# lcd_ch.net
KiCad netlist of a schematic drawn in Altium Designer
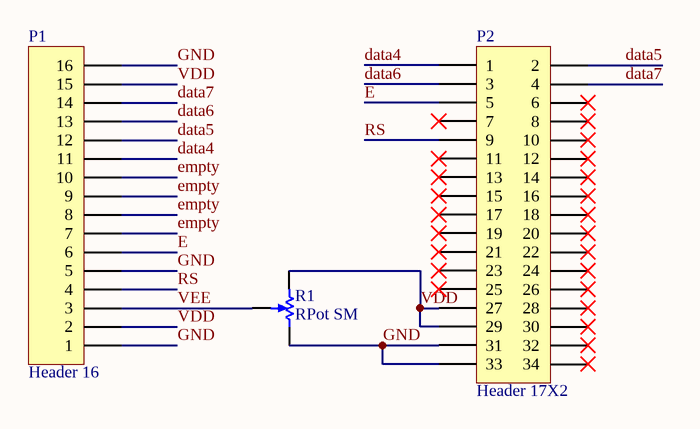
[diagram p0: lcd_ch.SchDoc]

(export (version "E")
  (design (tool "Eeschema 10.0.6"))
  (components
    (comp (ref "P1")
      (value "Header 16")
      (footprint "HDR1X16")
      (description "Header, 16-Pin")
      (fields (field (name "PUBLISHER") "Altium Limited"))
      (libsource (lib "Miscellaneous Connectors") (part "Header 16"))
    )
    (comp (ref "P2")
      (value "Header 17X2")
      (footprint "HDR2X17")
      (description "Header, 17-Pin, Dual row")
      (fields (field (name "PUBLISHER") "Altium Limited"))
      (libsource (lib "Miscellaneous Connectors") (part "Header 17X2"))
    )
    (comp (ref "R1")
      (value "RPot SM")
      (footprint "pot")
      (description "Square Trimming Potentiometer")
      (fields (field (name "PUBLISHER") "Altium Limited"))
      (libsource (lib "Miscellaneous Devices") (part "RPot SM"))
    )
  )
  (nets
    (net (code "2") (name "/E") (class "Default")
      (node (ref "P1") (pin "6") (pinfunction "6_6") (pintype "passive"))
      (node (ref "P2") (pin "5") (pinfunction "5_5") (pintype "passive"))
    )
    (net (code "3") (name "/GND") (class "Default")
      (node (ref "P1") (pin "1") (pinfunction "1_1") (pintype "passive"))
      (node (ref "P1") (pin "16") (pinfunction "16_16") (pintype "passive"))
      (node (ref "P1") (pin "5") (pinfunction "5_5") (pintype "passive"))
      (node (ref "P2") (pin "31") (pinfunction "31_31") (pintype "passive"))
      (node (ref "P2") (pin "33") (pinfunction "33_33") (pintype "passive"))
      (node (ref "R1") (pin "CW") (pinfunction "+_CW") (pintype "passive"))
    )
    (net (code "4") (name "/RS") (class "Default")
      (node (ref "P1") (pin "4") (pinfunction "4_4") (pintype "passive"))
      (node (ref "P2") (pin "9") (pinfunction "9_9") (pintype "passive"))
    )
    (net (code "5") (name "/VDD") (class "Default")
      (node (ref "P1") (pin "15") (pinfunction "15_15") (pintype "passive"))
      (node (ref "P1") (pin "2") (pinfunction "2_2") (pintype "passive"))
      (node (ref "P2") (pin "27") (pinfunction "27_27") (pintype "passive"))
      (node (ref "P2") (pin "29") (pinfunction "29_29") (pintype "passive"))
      (node (ref "R1") (pin "CCW") (pinfunction "-_CCW") (pintype "passive"))
    )
    (net (code "6") (name "/VEE") (class "Default")
      (node (ref "P1") (pin "3") (pinfunction "3_3") (pintype "passive"))
      (node (ref "R1") (pin "W") (pinfunction "W_W") (pintype "passive"))
    )
    (net (code "7") (name "/data4") (class "Default")
      (node (ref "P1") (pin "11") (pinfunction "11_11") (pintype "passive"))
      (node (ref "P2") (pin "1") (pinfunction "1_1") (pintype "passive"))
    )
    (net (code "8") (name "/data5") (class "Default")
      (node (ref "P1") (pin "12") (pinfunction "12_12") (pintype "passive"))
      (node (ref "P2") (pin "2") (pinfunction "2_2") (pintype "passive"))
    )
    (net (code "9") (name "/data6") (class "Default")
      (node (ref "P1") (pin "13") (pinfunction "13_13") (pintype "passive"))
      (node (ref "P2") (pin "3") (pinfunction "3_3") (pintype "passive"))
    )
    (net (code "10") (name "/data7") (class "Default")
      (node (ref "P1") (pin "14") (pinfunction "14_14") (pintype "passive"))
      (node (ref "P2") (pin "4") (pinfunction "4_4") (pintype "passive"))
    )
    (net (code "11") (name "/empty") (class "Default")
      (node (ref "P1") (pin "10") (pinfunction "10_10") (pintype "passive"))
      (node (ref "P1") (pin "7") (pinfunction "7_7") (pintype "passive"))
      (node (ref "P1") (pin "8") (pinfunction "8_8") (pintype "passive"))
      (node (ref "P1") (pin "9") (pinfunction "9_9") (pintype "passive"))
    )
    (net (code "12") (name "unconnected-(P2-Pad6)") (class "Default")
      (node (ref "P2") (pin "6") (pinfunction "6_6") (pintype "passive+no_connect"))
    )
    (net (code "13") (name "unconnected-(P2-Pad7)") (class "Default")
      (node (ref "P2") (pin "7") (pinfunction "7_7") (pintype "passive+no_connect"))
    )
    (net (code "14") (name "unconnected-(P2-Pad8)") (class "Default")
      (node (ref "P2") (pin "8") (pinfunction "8_8") (pintype "passive+no_connect"))
    )
    (net (code "15") (name "unconnected-(P2-Pad10)") (class "Default")
      (node (ref "P2") (pin "10") (pinfunction "10_10") (pintype "passive+no_connect"))
    )
    (net (code "16") (name "unconnected-(P2-Pad11)") (class "Default")
      (node (ref "P2") (pin "11") (pinfunction "11_11") (pintype "passive+no_connect"))
    )
    (net (code "17") (name "unconnected-(P2-Pad12)") (class "Default")
      (node (ref "P2") (pin "12") (pinfunction "12_12") (pintype "passive+no_connect"))
    )
    (net (code "18") (name "unconnected-(P2-Pad13)") (class "Default")
      (node (ref "P2") (pin "13") (pinfunction "13_13") (pintype "passive+no_connect"))
    )
    (net (code "19") (name "unconnected-(P2-Pad14)") (class "Default")
      (node (ref "P2") (pin "14") (pinfunction "14_14") (pintype "passive+no_connect"))
    )
    (net (code "20") (name "unconnected-(P2-Pad15)") (class "Default")
      (node (ref "P2") (pin "15") (pinfunction "15_15") (pintype "passive+no_connect"))
    )
    (net (code "21") (name "unconnected-(P2-Pad16)") (class "Default")
      (node (ref "P2") (pin "16") (pinfunction "16_16") (pintype "passive+no_connect"))
    )
    (net (code "22") (name "unconnected-(P2-Pad17)") (class "Default")
      (node (ref "P2") (pin "17") (pinfunction "17_17") (pintype "passive+no_connect"))
    )
    (net (code "23") (name "unconnected-(P2-Pad18)") (class "Default")
      (node (ref "P2") (pin "18") (pinfunction "18_18") (pintype "passive+no_connect"))
    )
    (net (code "24") (name "unconnected-(P2-Pad19)") (class "Default")
      (node (ref "P2") (pin "19") (pinfunction "19_19") (pintype "passive+no_connect"))
    )
    (net (code "25") (name "unconnected-(P2-Pad20)") (class "Default")
      (node (ref "P2") (pin "20") (pinfunction "20_20") (pintype "passive+no_connect"))
    )
    (net (code "26") (name "unconnected-(P2-Pad21)") (class "Default")
      (node (ref "P2") (pin "21") (pinfunction "21_21") (pintype "passive+no_connect"))
    )
    (net (code "27") (name "unconnected-(P2-Pad22)") (class "Default")
      (node (ref "P2") (pin "22") (pinfunction "22_22") (pintype "passive+no_connect"))
    )
    (net (code "28") (name "unconnected-(P2-Pad23)") (class "Default")
      (node (ref "P2") (pin "23") (pinfunction "23_23") (pintype "passive+no_connect"))
    )
    (net (code "29") (name "unconnected-(P2-Pad24)") (class "Default")
      (node (ref "P2") (pin "24") (pinfunction "24_24") (pintype "passive+no_connect"))
    )
    (net (code "30") (name "unconnected-(P2-Pad25)") (class "Default")
      (node (ref "P2") (pin "25") (pinfunction "25_25") (pintype "passive+no_connect"))
    )
    (net (code "31") (name "unconnected-(P2-Pad26)") (class "Default")
      (node (ref "P2") (pin "26") (pinfunction "26_26") (pintype "passive+no_connect"))
    )
    (net (code "32") (name "unconnected-(P2-Pad28)") (class "Default")
      (node (ref "P2") (pin "28") (pinfunction "28_28") (pintype "passive+no_connect"))
    )
    (net (code "33") (name "unconnected-(P2-Pad30)") (class "Default")
      (node (ref "P2") (pin "30") (pinfunction "30_30") (pintype "passive+no_connect"))
    )
    (net (code "34") (name "unconnected-(P2-Pad32)") (class "Default")
      (node (ref "P2") (pin "32") (pinfunction "32_32") (pintype "passive+no_connect"))
    )
    (net (code "35") (name "unconnected-(P2-Pad34)") (class "Default")
      (node (ref "P2") (pin "34") (pinfunction "34_34") (pintype "passive+no_connect"))
    )
  )
)
